# CoreCtrl.net
KiCad netlist of a schematic drawn in Altium Designer
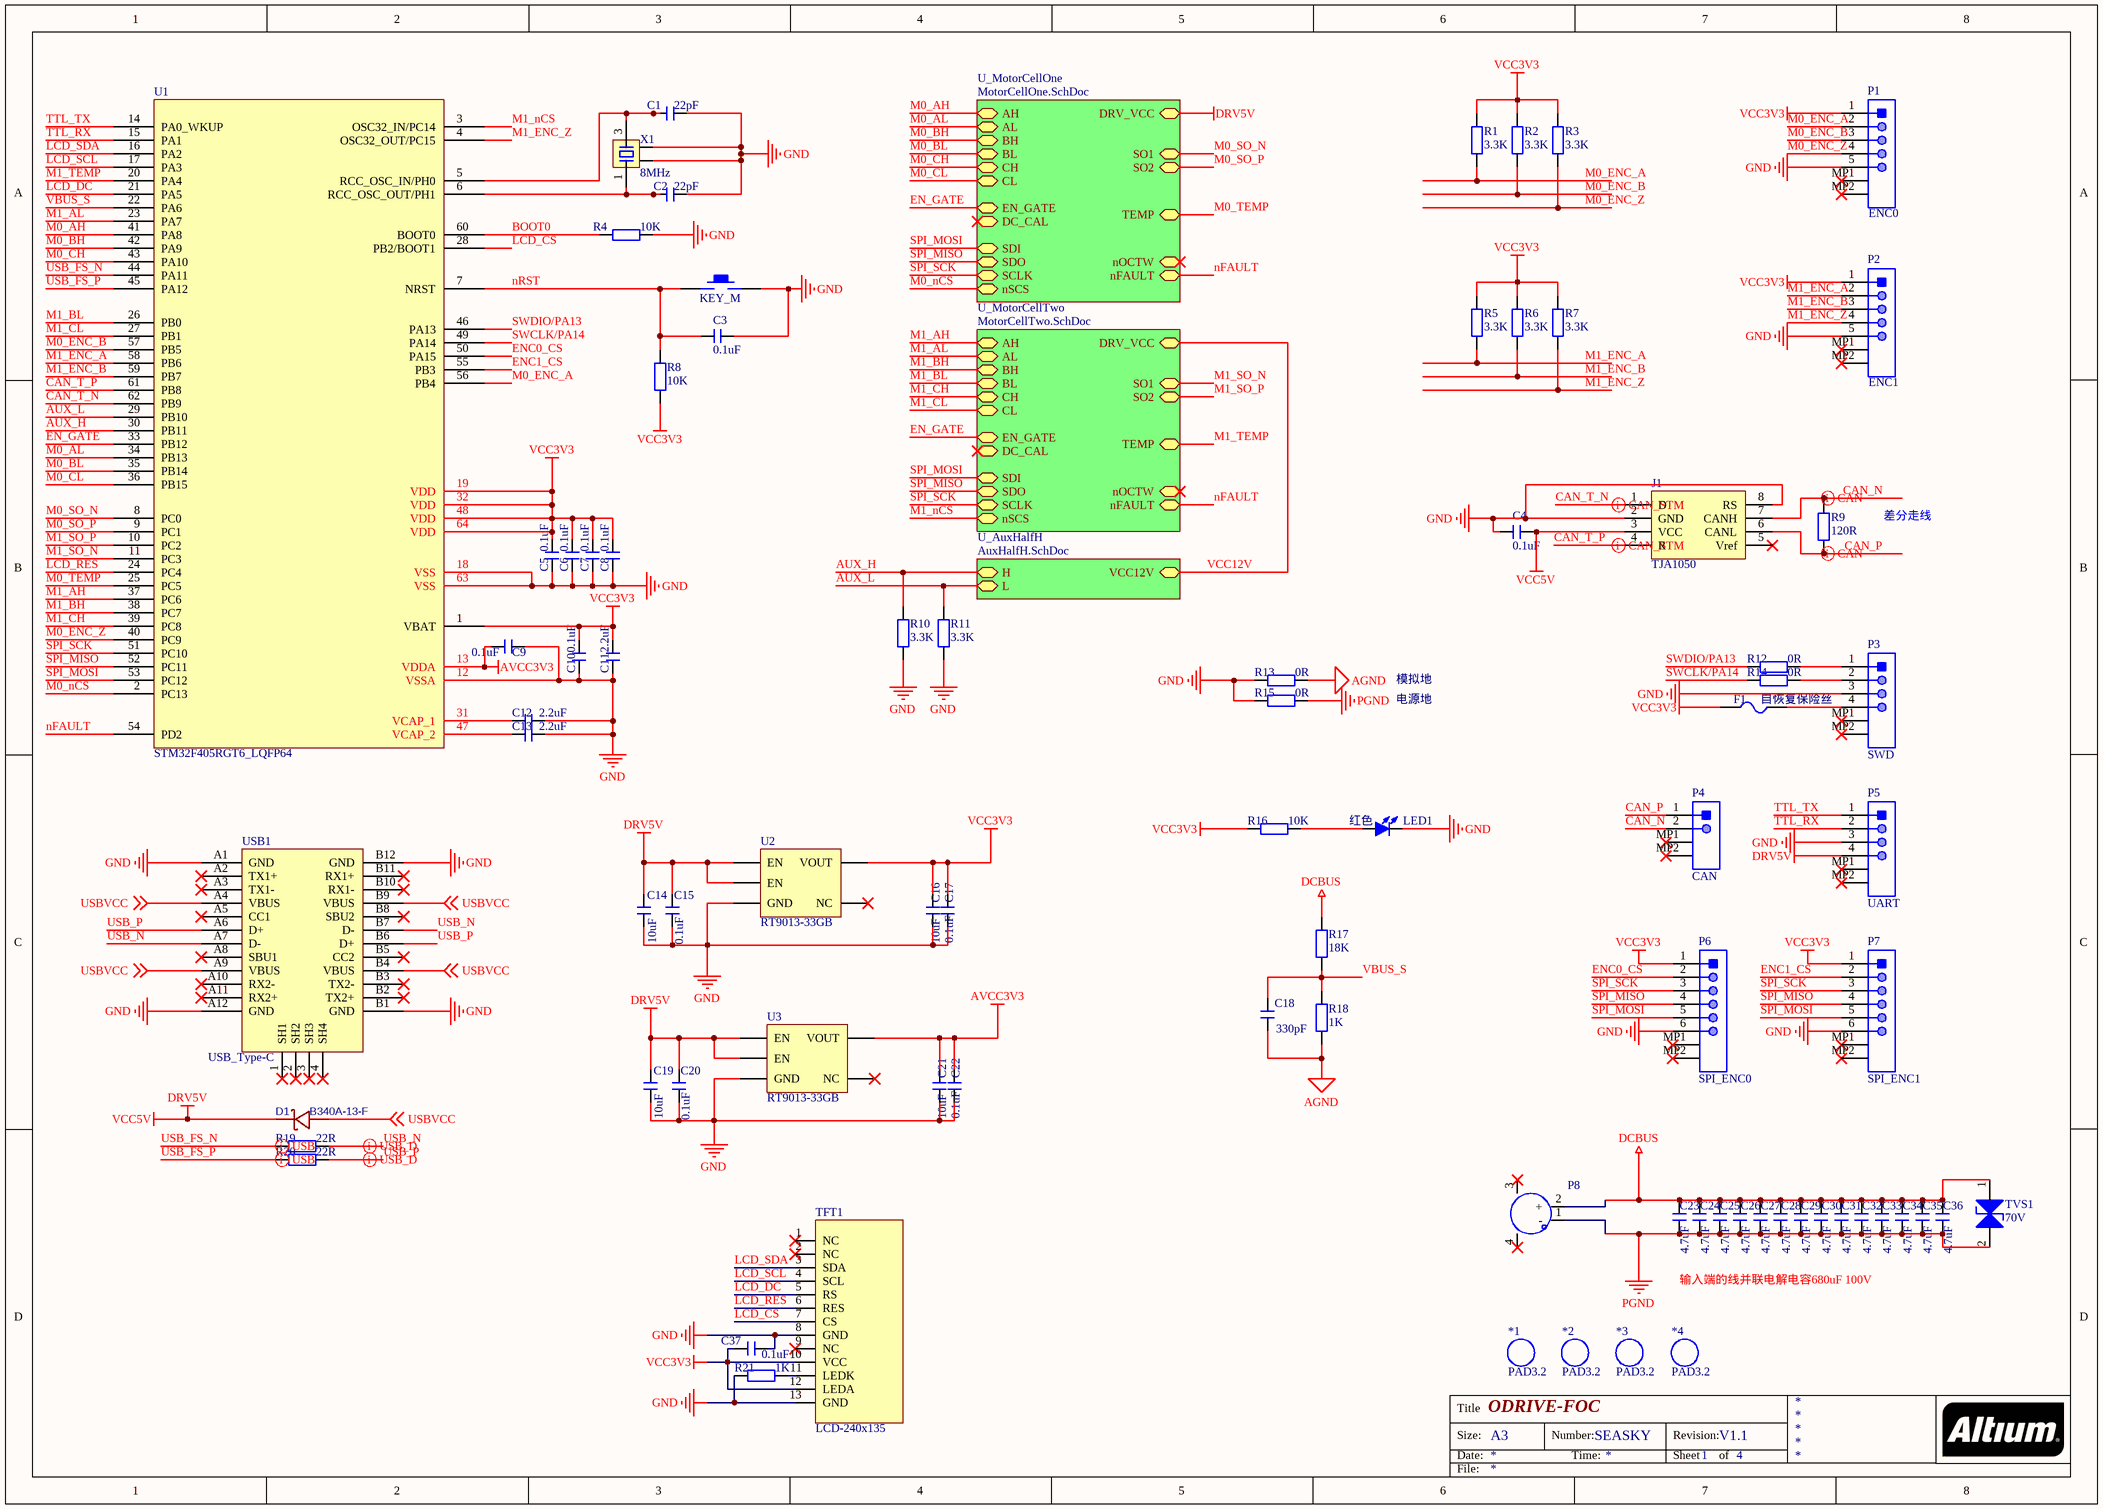
[diagram p0: CoreCtrl.SchDoc]

(export (version "E")
  (design (tool "Eeschema 10.0.6"))
  (components
    (comp (ref "*1") (value "PAD3.2") (footprint "PAD3.2") (libsource (lib "mx_pcb_library") (part "PAD3.2")))
    (comp (ref "*2") (value "PAD3.2") (footprint "PAD3.2") (libsource (lib "mx_pcb_library") (part "PAD3.2")))
    (comp (ref "*3") (value "PAD3.2") (footprint "PAD3.2") (libsource (lib "mx_pcb_library") (part "PAD3.2")))
    (comp (ref "*4") (value "PAD3.2") (footprint "PAD3.2") (libsource (lib "mx_pcb_library") (part "PAD3.2")))
    (comp (ref "C1")
      (value "22pF")
      (footprint "C 0603_L")
      (description "贴片电容")
      (libsource (lib "0.1 - 电阻-电容-电感") (part "C"))
    )
    (comp (ref "C2")
      (value "22pF")
      (footprint "C 0603_L")
      (description "贴片电容")
      (libsource (lib "0.1 - 电阻-电容-电感") (part "C"))
    )
    (comp (ref "C3")
      (value "0.1uF")
      (footprint "C 0603_L")
      (description "贴片电容")
      (libsource (lib "0.1 - 电阻-电容-电感") (part "C"))
    )
    (comp (ref "C4")
      (value "0.1uF")
      (footprint "C 0603_L")
      (description "贴片电容")
      (libsource (lib "0.1 - 电阻-电容-电感") (part "C"))
    )
    (comp (ref "C5")
      (value "0.1uF")
      (footprint "C 0603_L")
      (description "贴片电容")
      (libsource (lib "0.1 - 电阻-电容-电感") (part "C"))
    )
    (comp (ref "C6")
      (value "0.1uF")
      (footprint "C 0603_L")
      (description "贴片电容")
      (libsource (lib "0.1 - 电阻-电容-电感") (part "C"))
    )
    (comp (ref "C7")
      (value "0.1uF")
      (footprint "C 0603_L")
      (description "贴片电容")
      (libsource (lib "0.1 - 电阻-电容-电感") (part "C"))
    )
    (comp (ref "C8")
      (value "0.1uF")
      (footprint "C 0603_L")
      (description "贴片电容")
      (libsource (lib "0.1 - 电阻-电容-电感") (part "C"))
    )
    (comp (ref "C9")
      (value "0.1uF")
      (footprint "C 0603_L")
      (description "贴片电容")
      (libsource (lib "0.1 - 电阻-电容-电感") (part "C"))
    )
    (comp (ref "C10")
      (value "0.1uF")
      (footprint "C 0603_L")
      (description "贴片电容")
      (libsource (lib "0.1 - 电阻-电容-电感") (part "C"))
    )
    (comp (ref "C11")
      (value "2.2uF")
      (footprint "C 0603_L")
      (description "贴片电容")
      (libsource (lib "0.1 - 电阻-电容-电感") (part "C"))
    )
    (comp (ref "C12")
      (value "2.2uF")
      (footprint "C 0603_L")
      (description "贴片电容")
      (libsource (lib "0.1 - 电阻-电容-电感") (part "C"))
    )
    (comp (ref "C13")
      (value "2.2uF")
      (footprint "C 0603_L")
      (description "贴片电容")
      (libsource (lib "0.1 - 电阻-电容-电感") (part "C"))
    )
    (comp (ref "C14")
      (value "10uF")
      (footprint "C 0805_L")
      (description "贴片电容")
      (libsource (lib "0.1 - 电阻-电容-电感") (part "C"))
    )
    (comp (ref "C15")
      (value "0.1uF")
      (footprint "C 0805_L")
      (description "贴片电容")
      (libsource (lib "0.1 - 电阻-电容-电感") (part "C"))
    )
    (comp (ref "C16")
      (value "10uF")
      (footprint "C 0805_L")
      (description "贴片电容")
      (libsource (lib "0.1 - 电阻-电容-电感") (part "C"))
    )
    (comp (ref "C17")
      (value "0.1uF")
      (footprint "C 0805_L")
      (description "贴片电容")
      (libsource (lib "0.1 - 电阻-电容-电感") (part "C"))
    )
    (comp (ref "C18")
      (value "330pF")
      (footprint "C 0603_L")
      (description "贴片电容")
      (libsource (lib "0.1 - 电阻-电容-电感") (part "C"))
    )
    (comp (ref "C19")
      (value "10uF")
      (footprint "C 0805_L")
      (description "贴片电容")
      (libsource (lib "0.1 - 电阻-电容-电感") (part "C"))
    )
    (comp (ref "C20")
      (value "0.1uF")
      (footprint "C 0805_L")
      (description "贴片电容")
      (libsource (lib "0.1 - 电阻-电容-电感") (part "C"))
    )
    (comp (ref "C21")
      (value "10uF")
      (footprint "C 0805_L")
      (description "贴片电容")
      (libsource (lib "0.1 - 电阻-电容-电感") (part "C"))
    )
    (comp (ref "C22")
      (value "0.1uF")
      (footprint "C 0805_L")
      (description "贴片电容")
      (libsource (lib "0.1 - 电阻-电容-电感") (part "C"))
    )
    (comp (ref "C23")
      (value "4.7uF")
      (footprint "C 1210_L")
      (description "贴片电容")
      (libsource (lib "0.1 - 电阻-电容-电感") (part "C"))
    )
    (comp (ref "C24")
      (value "4.7uF")
      (footprint "C 1210_L")
      (description "贴片电容")
      (libsource (lib "0.1 - 电阻-电容-电感") (part "C"))
    )
    (comp (ref "C25")
      (value "4.7uF")
      (footprint "C 1210_L")
      (description "贴片电容")
      (libsource (lib "0.1 - 电阻-电容-电感") (part "C"))
    )
    (comp (ref "C26")
      (value "4.7uF")
      (footprint "C 1210_L")
      (description "贴片电容")
      (libsource (lib "0.1 - 电阻-电容-电感") (part "C"))
    )
    (comp (ref "C27")
      (value "4.7uF")
      (footprint "C 1210_L")
      (description "贴片电容")
      (libsource (lib "0.1 - 电阻-电容-电感") (part "C"))
    )
    (comp (ref "C28")
      (value "4.7uF")
      (footprint "C 1210_L")
      (description "贴片电容")
      (libsource (lib "0.1 - 电阻-电容-电感") (part "C"))
    )
    (comp (ref "C29")
      (value "4.7uF")
      (footprint "C 1210_L")
      (description "贴片电容")
      (libsource (lib "0.1 - 电阻-电容-电感") (part "C"))
    )
    (comp (ref "C30")
      (value "4.7uF")
      (footprint "C 1210_L")
      (description "贴片电容")
      (libsource (lib "0.1 - 电阻-电容-电感") (part "C"))
    )
    (comp (ref "C31")
      (value "4.7uF")
      (footprint "C 1210_L")
      (description "贴片电容")
      (libsource (lib "0.1 - 电阻-电容-电感") (part "C"))
    )
    (comp (ref "C32")
      (value "4.7uF")
      (footprint "C 1210_L")
      (description "贴片电容")
      (libsource (lib "0.1 - 电阻-电容-电感") (part "C"))
    )
    (comp (ref "C33")
      (value "4.7uF")
      (footprint "C 1210_L")
      (description "贴片电容")
      (libsource (lib "0.1 - 电阻-电容-电感") (part "C"))
    )
    (comp (ref "C34")
      (value "4.7uF")
      (footprint "C 1210_L")
      (description "贴片电容")
      (libsource (lib "0.1 - 电阻-电容-电感") (part "C"))
    )
    (comp (ref "C35")
      (value "4.7uF")
      (footprint "C 1210_L")
      (description "贴片电容")
      (libsource (lib "0.1 - 电阻-电容-电感") (part "C"))
    )
    (comp (ref "C36")
      (value "4.7uF")
      (footprint "C 1210_L")
      (description "贴片电容")
      (libsource (lib "0.1 - 电阻-电容-电感") (part "C"))
    )
    (comp (ref "C37")
      (value "0.1uF")
      (footprint "C 0603_L")
      (description "贴片电容")
      (libsource (lib "0.1 - 电阻-电容-电感") (part "C"))
    )
    (comp (ref "D1")
      (value "B340A-13-F")
      (footprint "SMA_L4.4-W2.6-LS5.0-RD")
      (fields (field (name "BOM_SUPPLIER PART") "C85098"))
      (libsource (lib "mx_pcb_library") (part "B340A-13-F"))
    )
    (comp (ref "F1")
      (value "自恢复保险丝")
      (footprint "FU 0603")
      (description "贴片保险丝")
      (libsource (lib "2.0 - 保险丝-晶振-光耦") (part "FU"))
    )
    (comp (ref "J1")
      (value "TJA1050")
      (footprint "SOIC-8_150mil")
      (description "CAN芯片")
      (libsource (lib "mx_pcb_library") (part "TJA1050"))
    )
    (comp (ref "LED1")
      (value "红色")
      (footprint "LED 0805G")
      (description "贴片LED")
      (libsource (lib "0.3 - LED发光二极管") (part "LED-SMD"))
    )
    (comp (ref "P1")
      (value "ENC0")
      (footprint "JST-SM05B-GHS-TB_V")
      (fields (field (name "MANUFACTURER") "JST"))
      (libsource (lib "JST GH connector") (part "SM05B-GHS-TB(LF)(SN)"))
    )
    (comp (ref "P2")
      (value "ENC1")
      (footprint "JST-SM05B-GHS-TB_V")
      (fields (field (name "MANUFACTURER") "JST"))
      (libsource (lib "JST GH connector") (part "SM05B-GHS-TB(LF)(SN)"))
    )
    (comp (ref "P3")
      (value "SWD")
      (footprint "JST-SM04B-GHS-TB_V")
      (fields (field (name "MANUFACTURER") "JST"))
      (libsource (lib "JST GH connector") (part "SM04B-GHS-TB(LF)(SN)"))
    )
    (comp (ref "P4")
      (value "CAN")
      (footprint "CONN-SMD_SM02B-GHS-TB-LF-SN")
      (libsource (lib "ODrive_Foc") (part "SM02B-GHS-TB(LF)(SN)"))
    )
    (comp (ref "P5")
      (value "UART")
      (footprint "JST-SM04B-GHS-TB_V")
      (fields (field (name "MANUFACTURER") "JST"))
      (libsource (lib "JST GH connector") (part "SM04B-GHS-TB(LF)(SN)"))
    )
    (comp (ref "P6")
      (value "SPI_ENC0")
      (footprint "JST-BM06B-GHS-TBT_V")
      (fields (field (name "MANUFACTURER") "JST"))
      (libsource (lib "JST GH connector") (part "SM06B-GHS-TB(LF)(SN)"))
    )
    (comp (ref "P7")
      (value "SPI_ENC1")
      (footprint "JST-BM06B-GHS-TBT_V")
      (fields (field (name "MANUFACTURER") "JST"))
      (libsource (lib "JST GH connector") (part "BM06B-GHS-TBT(LF)(SN)"))
    )
    (comp (ref "P8") (value "XT60PW") (footprint "XT60PW") (libsource (lib "ODrive_Foc") (part "XT60PW")))
    (comp (ref "R1")
      (value "3.3K")
      (footprint "R 0603_L")
      (description "贴片电阻")
      (libsource (lib "0.1 - 电阻-电容-电感") (part "R"))
    )
    (comp (ref "R2")
      (value "3.3K")
      (footprint "R 0603_L")
      (description "贴片电阻")
      (libsource (lib "0.1 - 电阻-电容-电感") (part "R"))
    )
    (comp (ref "R3")
      (value "3.3K")
      (footprint "R 0603_L")
      (description "贴片电阻")
      (libsource (lib "0.1 - 电阻-电容-电感") (part "R"))
    )
    (comp (ref "R4")
      (value "10K")
      (footprint "R 0603_L")
      (description "贴片电阻")
      (libsource (lib "0.1 - 电阻-电容-电感") (part "R"))
    )
    (comp (ref "R5")
      (value "3.3K")
      (footprint "R 0603_L")
      (description "贴片电阻")
      (libsource (lib "0.1 - 电阻-电容-电感") (part "R"))
    )
    (comp (ref "R6")
      (value "3.3K")
      (footprint "R 0603_L")
      (description "贴片电阻")
      (libsource (lib "0.1 - 电阻-电容-电感") (part "R"))
    )
    (comp (ref "R7")
      (value "3.3K")
      (footprint "R 0603_L")
      (description "贴片电阻")
      (libsource (lib "0.1 - 电阻-电容-电感") (part "R"))
    )
    (comp (ref "R8")
      (value "10K")
      (footprint "R 0603_L")
      (description "贴片电阻")
      (libsource (lib "0.1 - 电阻-电容-电感") (part "R"))
    )
    (comp (ref "R9")
      (value "120R")
      (footprint "R 0603_L")
      (description "贴片电阻")
      (libsource (lib "0.1 - 电阻-电容-电感") (part "R"))
    )
    (comp (ref "R10")
      (value "3.3K")
      (footprint "R 0603_L")
      (description "贴片电阻")
      (libsource (lib "0.1 - 电阻-电容-电感") (part "R"))
    )
    (comp (ref "R11")
      (value "3.3K")
      (footprint "R 0603_L")
      (description "贴片电阻")
      (libsource (lib "0.1 - 电阻-电容-电感") (part "R"))
    )
    (comp (ref "R12")
      (value "0R")
      (footprint "R 0603_L")
      (description "贴片电阻")
      (libsource (lib "0.1 - 电阻-电容-电感") (part "R"))
    )
    (comp (ref "R13")
      (value "0R")
      (footprint "R 0603_L")
      (description "贴片电阻")
      (libsource (lib "0.1 - 电阻-电容-电感") (part "R"))
    )
    (comp (ref "R14")
      (value "0R")
      (footprint "R 0603_L")
      (description "贴片电阻")
      (libsource (lib "0.1 - 电阻-电容-电感") (part "R"))
    )
    (comp (ref "R15")
      (value "0R")
      (footprint "R 0603_L")
      (description "贴片电阻")
      (libsource (lib "0.1 - 电阻-电容-电感") (part "R"))
    )
    (comp (ref "R16")
      (value "10K")
      (footprint "R 0603_L")
      (description "贴片电阻")
      (libsource (lib "0.1 - 电阻-电容-电感") (part "R"))
    )
    (comp (ref "R17")
      (value "18K")
      (footprint "R 0603_L")
      (description "贴片电阻")
      (libsource (lib "0.1 - 电阻-电容-电感") (part "R"))
    )
    (comp (ref "R18")
      (value "1K")
      (footprint "R 0603_L")
      (description "贴片电阻")
      (libsource (lib "0.1 - 电阻-电容-电感") (part "R"))
    )
    (comp (ref "R19")
      (value "22R")
      (footprint "R 0603_L")
      (description "贴片电阻")
      (libsource (lib "0.1 - 电阻-电容-电感") (part "R"))
    )
    (comp (ref "R20")
      (value "22R")
      (footprint "R 0603_L")
      (description "贴片电阻")
      (libsource (lib "0.1 - 电阻-电容-电感") (part "R"))
    )
    (comp (ref "R21")
      (value "1K")
      (footprint "R 0603_L")
      (description "贴片电阻")
      (libsource (lib "0.1 - 电阻-电容-电感") (part "R"))
    )
    (comp (ref "RST1")
      (value "KEY_M")
      (footprint "SMD-3.2*4.2")
      (libsource (lib "mx_pcb_library") (part "KEY_M"))
    )
    (comp (ref "TFT1")
      (value "LCD-240x135")
      (footprint "LCD-240x135")
      (libsource (lib "ODrive_Foc") (part "LCD-240x135"))
    )
    (comp (ref "TVS1")
      (value "70V")
      (footprint "SMA(DO-214AC)")
      (libsource (lib "mx_pcb_library") (part "SMAJ28CA"))
    )
    (comp (ref "U1")
      (value "STM32F405RGT6_LQFP64")
      (footprint "LQFP-64_10X10X05P")
      (libsource (lib "mx_pcb_library") (part "STM32F405RGT6_LQFP64"))
    )
    (comp (ref "U2")
      (value "RT9013-33GB")
      (footprint "SOT23-5M")
      (libsource (lib "mx_pcb_library") (part "RT9013-33GB"))
    )
    (comp (ref "U3")
      (value "RT9013-33GB")
      (footprint "SOT23-5M")
      (libsource (lib "mx_pcb_library") (part "RT9013-33GB"))
    )
    (comp (ref "USB1")
      (value "USB_Type-C")
      (footprint "Type-C-TOP")
      (libsource (lib "mx_pcb_library") (part "USB_Type-C"))
    )
    (comp (ref "X1")
      (value "8MHz")
      (footprint "OSC 3225-4P")
      (description "4脚无源晶振")
      (libsource (lib "2.0 - 保险丝-晶振-光耦") (part "XTAL-4P"))
    )
  )
  (nets
    (net (code "1") (name "/AUX_H") (class "Default")
      (node (ref "R10") (pin "1") (pinfunction "1_1") (pintype "passive"))
      (node (ref "U1") (pin "30") (pinfunction "PB11_30") (pintype "passive"))
    )
    (net (code "2") (name "/AUX_L") (class "Default")
      (node (ref "R11") (pin "1") (pinfunction "1_1") (pintype "passive"))
      (node (ref "U1") (pin "29") (pinfunction "PB10_29") (pintype "passive"))
    )
    (net (code "3") (name "/BOOT0") (class "Default")
      (node (ref "R4") (pin "2") (pinfunction "2_2") (pintype "passive"))
      (node (ref "U1") (pin "60") (pinfunction "BOOT0_60") (pintype "passive"))
    )
    (net (code "4") (name "/CAN_N") (class "Default")
      (node (ref "J1") (pin "7") (pinfunction "CANH_7") (pintype "passive"))
      (node (ref "P4") (pin "2") (pinfunction "2_2") (pintype "passive"))
      (node (ref "R9") (pin "1") (pinfunction "1_1") (pintype "passive"))
    )
    (net (code "5") (name "/CAN_P") (class "Default")
      (node (ref "J1") (pin "6") (pinfunction "CANL_6") (pintype "passive"))
      (node (ref "P4") (pin "1") (pinfunction "1_1") (pintype "passive"))
      (node (ref "R9") (pin "2") (pinfunction "2_2") (pintype "passive"))
    )
    (net (code "6") (name "/CAN_T_N") (class "Default")
      (node (ref "J1") (pin "1") (pinfunction "D_1") (pintype "passive"))
      (node (ref "U1") (pin "62") (pinfunction "PB9_62") (pintype "passive"))
    )
    (net (code "7") (name "/CAN_T_P") (class "Default")
      (node (ref "J1") (pin "4") (pinfunction "R_4") (pintype "passive"))
      (node (ref "U1") (pin "61") (pinfunction "PB8_61") (pintype "passive"))
    )
    (net (code "10") (name "/ENC0_CS") (class "Default")
      (node (ref "P6") (pin "2") (pinfunction "2_2") (pintype "passive"))
      (node (ref "U1") (pin "50") (pinfunction "PA15_50") (pintype "passive"))
    )
    (net (code "11") (name "/ENC1_CS") (class "Default")
      (node (ref "P7") (pin "2") (pinfunction "2_2") (pintype "passive"))
      (node (ref "U1") (pin "55") (pinfunction "PB3_55") (pintype "passive"))
    )
    (net (code "12") (name "/EN_GATE") (class "Default")
      (node (ref "U1") (pin "33") (pinfunction "PB12_33") (pintype "passive"))
    )
    (net (code "13") (name "/LCD_CS") (class "Default")
      (node (ref "TFT1") (pin "7") (pinfunction "CS_7") (pintype "passive"))
      (node (ref "U1") (pin "28") (pinfunction "PB2/BOOT1_28") (pintype "passive"))
    )
    (net (code "14") (name "/LCD_DC") (class "Default")
      (node (ref "TFT1") (pin "5") (pinfunction "RS_5") (pintype "passive"))
      (node (ref "U1") (pin "21") (pinfunction "PA5_21") (pintype "passive"))
    )
    (net (code "15") (name "/LCD_RES") (class "Default")
      (node (ref "TFT1") (pin "6") (pinfunction "RES_6") (pintype "passive"))
      (node (ref "U1") (pin "24") (pinfunction "PC4_24") (pintype "passive"))
    )
    (net (code "16") (name "/LCD_SCL") (class "Default")
      (node (ref "TFT1") (pin "4") (pinfunction "SCL_4") (pintype "passive"))
      (node (ref "U1") (pin "17") (pinfunction "PA3_17") (pintype "passive"))
    )
    (net (code "17") (name "/LCD_SDA") (class "Default")
      (node (ref "TFT1") (pin "3") (pinfunction "SDA_3") (pintype "passive"))
      (node (ref "U1") (pin "16") (pinfunction "PA2_16") (pintype "passive"))
    )
    (net (code "18") (name "/M0_AH") (class "Default")
      (node (ref "U1") (pin "41") (pinfunction "PA8_41") (pintype "passive"))
    )
    (net (code "19") (name "/M0_AL") (class "Default")
      (node (ref "U1") (pin "34") (pinfunction "PB13_34") (pintype "passive"))
    )
    (net (code "20") (name "/M0_BH") (class "Default")
      (node (ref "U1") (pin "42") (pinfunction "PA9_42") (pintype "passive"))
    )
    (net (code "21") (name "/M0_BL") (class "Default")
      (node (ref "U1") (pin "35") (pinfunction "PB14_35") (pintype "passive"))
    )
    (net (code "22") (name "/M0_CH") (class "Default")
      (node (ref "U1") (pin "43") (pinfunction "PA10_43") (pintype "passive"))
    )
    (net (code "23") (name "/M0_CL") (class "Default")
      (node (ref "U1") (pin "36") (pinfunction "PB15_36") (pintype "passive"))
    )
    (net (code "24") (name "/M0_ENC_A") (class "Default")
      (node (ref "P1") (pin "2") (pinfunction "2_2") (pintype "passive"))
      (node (ref "R1") (pin "2") (pinfunction "2_2") (pintype "passive"))
      (node (ref "U1") (pin "56") (pinfunction "PB4_56") (pintype "passive"))
    )
    (net (code "25") (name "/M0_ENC_B") (class "Default")
      (node (ref "P1") (pin "3") (pinfunction "3_3") (pintype "passive"))
      (node (ref "R2") (pin "2") (pinfunction "2_2") (pintype "passive"))
      (node (ref "U1") (pin "57") (pinfunction "PB5_57") (pintype "passive"))
    )
    (net (code "26") (name "/M0_ENC_Z") (class "Default")
      (node (ref "P1") (pin "4") (pinfunction "4_4") (pintype "passive"))
      (node (ref "R3") (pin "2") (pinfunction "2_2") (pintype "passive"))
      (node (ref "U1") (pin "40") (pinfunction "PC9_40") (pintype "passive"))
    )
    (net (code "27") (name "/M0_SO_N") (class "Default")
      (node (ref "U1") (pin "8") (pinfunction "PC0_8") (pintype "passive"))
    )
    (net (code "28") (name "/M0_SO_P") (class "Default")
      (node (ref "U1") (pin "9") (pinfunction "PC1_9") (pintype "passive"))
    )
    (net (code "29") (name "/M0_TEMP") (class "Default")
      (node (ref "U1") (pin "25") (pinfunction "PC5_25") (pintype "passive"))
    )
    (net (code "30") (name "/M0_nCS") (class "Default")
      (node (ref "U1") (pin "2") (pinfunction "PC13_2") (pintype "passive"))
    )
    (net (code "31") (name "/M1_AH") (class "Default")
      (node (ref "U1") (pin "37") (pinfunction "PC6_37") (pintype "passive"))
    )
    (net (code "32") (name "/M1_AL") (class "Default")
      (node (ref "U1") (pin "23") (pinfunction "PA7_23") (pintype "passive"))
    )
    (net (code "33") (name "/M1_BH") (class "Default")
      (node (ref "U1") (pin "38") (pinfunction "PC7_38") (pintype "passive"))
    )
    (net (code "34") (name "/M1_BL") (class "Default")
      (node (ref "U1") (pin "26") (pinfunction "PB0_26") (pintype "passive"))
    )
    (net (code "35") (name "/M1_CH") (class "Default")
      (node (ref "U1") (pin "39") (pinfunction "PC8_39") (pintype "passive"))
    )
    (net (code "36") (name "/M1_CL") (class "Default")
      (node (ref "U1") (pin "27") (pinfunction "PB1_27") (pintype "passive"))
    )
    (net (code "37") (name "/M1_ENC_A") (class "Default")
      (node (ref "P2") (pin "2") (pinfunction "2_2") (pintype "passive"))
      (node (ref "R5") (pin "2") (pinfunction "2_2") (pintype "passive"))
      (node (ref "U1") (pin "58") (pinfunction "PB6_58") (pintype "passive"))
    )
    (net (code "38") (name "/M1_ENC_B") (class "Default")
      (node (ref "P2") (pin "3") (pinfunction "3_3") (pintype "passive"))
      (node (ref "R6") (pin "2") (pinfunction "2_2") (pintype "passive"))
      (node (ref "U1") (pin "59") (pinfunction "PB7_59") (pintype "passive"))
    )
    (net (code "39") (name "/M1_ENC_Z") (class "Default")
      (node (ref "P2") (pin "4") (pinfunction "4_4") (pintype "passive"))
      (node (ref "R7") (pin "2") (pinfunction "2_2") (pintype "passive"))
      (node (ref "U1") (pin "4") (pinfunction "OSC32_OUT/PC15_4") (pintype "passive"))
    )
    (net (code "40") (name "/M1_SO_N") (class "Default")
      (node (ref "U1") (pin "11") (pinfunction "PC3_11") (pintype "passive"))
    )
    (net (code "41") (name "/M1_SO_P") (class "Default")
      (node (ref "U1") (pin "10") (pinfunction "PC2_10") (pintype "passive"))
    )
    (net (code "42") (name "/M1_TEMP") (class "Default")
      (node (ref "U1") (pin "20") (pinfunction "PA4_20") (pintype "passive"))
    )
    (net (code "43") (name "/M1_nCS") (class "Default")
      (node (ref "U1") (pin "3") (pinfunction "OSC32_IN/PC14_3") (pintype "passive"))
    )
    (net (code "44") (name "/SPI_MISO") (class "Default")
      (node (ref "P6") (pin "4") (pinfunction "4_4") (pintype "passive"))
      (node (ref "P7") (pin "4") (pinfunction "4_4") (pintype "passive"))
      (node (ref "U1") (pin "52") (pinfunction "PC11_52") (pintype "passive"))
    )
    (net (code "45") (name "/SPI_MOSI") (class "Default")
      (node (ref "P6") (pin "5") (pinfunction "5_5") (pintype "passive"))
      (node (ref "P7") (pin "5") (pinfunction "5_5") (pintype "passive"))
      (node (ref "U1") (pin "53") (pinfunction "PC12_53") (pintype "passive"))
    )
    (net (code "46") (name "/SPI_SCK") (class "Default")
      (node (ref "P6") (pin "3") (pinfunction "3_3") (pintype "passive"))
      (node (ref "P7") (pin "3") (pinfunction "3_3") (pintype "passive"))
      (node (ref "U1") (pin "51") (pinfunction "PC10_51") (pintype "passive"))
    )
    (net (code "47") (name "/SWCLK{slash}PA14") (class "Default")
      (node (ref "R14") (pin "2") (pinfunction "2_2") (pintype "passive"))
      (node (ref "U1") (pin "49") (pinfunction "PA14_49") (pintype "passive"))
    )
    (net (code "48") (name "/SWDIO{slash}PA13") (class "Default")
      (node (ref "R12") (pin "2") (pinfunction "2_2") (pintype "passive"))
      (node (ref "U1") (pin "46") (pinfunction "PA13_46") (pintype "passive"))
    )
    (net (code "49") (name "/TTL_RX") (class "Default")
      (node (ref "P5") (pin "2") (pinfunction "2_2") (pintype "passive"))
      (node (ref "U1") (pin "15") (pinfunction "PA1_15") (pintype "passive"))
    )
    (net (code "50") (name "/TTL_TX") (class "Default")
      (node (ref "P5") (pin "1") (pinfunction "1_1") (pintype "passive"))
      (node (ref "U1") (pin "14") (pinfunction "PA0_WKUP_14") (pintype "passive"))
    )
    (net (code "51") (name "/USB_FS_N") (class "Default")
      (node (ref "R19") (pin "1") (pinfunction "1_1") (pintype "passive"))
      (node (ref "U1") (pin "44") (pinfunction "PA11_44") (pintype "passive"))
    )
    (net (code "52") (name "/USB_FS_P") (class "Default")
      (node (ref "R20") (pin "1") (pinfunction "1_1") (pintype "passive"))
      (node (ref "U1") (pin "45") (pinfunction "PA12_45") (pintype "passive"))
    )
    (net (code "53") (name "/USB_N") (class "Default")
      (node (ref "R19") (pin "2") (pinfunction "2_2") (pintype "passive"))
      (node (ref "USB1") (pin "A7") (pinfunction "D-_A7") (pintype "passive"))
      (node (ref "USB1") (pin "B7") (pinfunction "D-_B7") (pintype "passive"))
    )
    (net (code "54") (name "/USB_P") (class "Default")
      (node (ref "R20") (pin "2") (pinfunction "2_2") (pintype "passive"))
      (node (ref "USB1") (pin "A6") (pinfunction "D+_A6") (pintype "passive"))
      (node (ref "USB1") (pin "B6") (pinfunction "D+_B6") (pintype "passive"))
    )
    (net (code "55") (name "/VBUS_S") (class "Default")
      (node (ref "C18") (pin "1") (pinfunction "1_1") (pintype "passive"))
      (node (ref "R17") (pin "2") (pinfunction "2_2") (pintype "passive"))
      (node (ref "R18") (pin "1") (pinfunction "1_1") (pintype "passive"))
      (node (ref "U1") (pin "22") (pinfunction "PA6_22") (pintype "passive"))
    )
    (net (code "57") (name "/nFAULT") (class "Default")
      (node (ref "U1") (pin "54") (pinfunction "PD2_54") (pintype "passive"))
    )
    (net (code "60") (name "/nRST") (class "Default")
      (node (ref "C3") (pin "2") (pinfunction "2_2") (pintype "passive"))
      (node (ref "R8") (pin "2") (pinfunction "2_2") (pintype "passive"))
      (node (ref "RST1") (pin "1") (pinfunction "1_1") (pintype "passive"))
      (node (ref "U1") (pin "7") (pinfunction "NRST_7") (pintype "passive"))
    )
    (net (code "61") (name "AGND") (class "Default")
      (node (ref "C18") (pin "2") (pinfunction "2_2") (pintype "passive"))
      (node (ref "R13") (pin "1") (pinfunction "1_1") (pintype "passive"))
      (node (ref "R18") (pin "2") (pinfunction "2_2") (pintype "passive"))
    )
    (net (code "62") (name "AVCC3V3") (class "Default")
      (node (ref "C21") (pin "2") (pinfunction "2_2") (pintype "passive"))
      (node (ref "C22") (pin "2") (pinfunction "2_2") (pintype "passive"))
      (node (ref "C9") (pin "2") (pinfunction "2_2") (pintype "passive"))
      (node (ref "U1") (pin "13") (pinfunction "VDDA_13") (pintype "passive"))
      (node (ref "U3") (pin "5") (pinfunction "VOUT_5") (pintype "passive"))
    )
    (net (code "63") (name "DCBUS") (class "Default")
      (node (ref "C23") (pin "2") (pinfunction "2_2") (pintype "passive"))
      (node (ref "C24") (pin "2") (pinfunction "2_2") (pintype "passive"))
      (node (ref "C25") (pin "2") (pinfunction "2_2") (pintype "passive"))
      (node (ref "C26") (pin "2") (pinfunction "2_2") (pintype "passive"))
      (node (ref "C27") (pin "2") (pinfunction "2_2") (pintype "passive"))
      (node (ref "C28") (pin "2") (pinfunction "2_2") (pintype "passive"))
      (node (ref "C29") (pin "2") (pinfunction "2_2") (pintype "passive"))
      (node (ref "C30") (pin "2") (pinfunction "2_2") (pintype "passive"))
      (node (ref "C31") (pin "2") (pinfunction "2_2") (pintype "passive"))
      (node (ref "C32") (pin "2") (pinfunction "2_2") (pintype "passive"))
      (node (ref "C33") (pin "2") (pinfunction "2_2") (pintype "passive"))
      (node (ref "C34") (pin "2") (pinfunction "2_2") (pintype "passive"))
      (node (ref "C35") (pin "2") (pinfunction "2_2") (pintype "passive"))
      (node (ref "C36") (pin "2") (pinfunction "2_2") (pintype "passive"))
      (node (ref "P8") (pin "2") (pinfunction "+_2") (pintype "passive"))
      (node (ref "R17") (pin "1") (pinfunction "1_1") (pintype "passive"))
      (node (ref "TVS1") (pin "1") (pinfunction "1_1") (pintype "passive"))
    )
    (net (code "64") (name "DRV5V") (class "Default")
      (node (ref "C14") (pin "2") (pinfunction "2_2") (pintype "passive"))
      (node (ref "C15") (pin "2") (pinfunction "2_2") (pintype "passive"))
      (node (ref "C19") (pin "2") (pinfunction "2_2") (pintype "passive"))
      (node (ref "C20") (pin "2") (pinfunction "2_2") (pintype "passive"))
      (node (ref "C4") (pin "1") (pinfunction "1_1") (pintype "passive"))
      (node (ref "D1") (pin "1") (pinfunction "K_1") (pintype "passive"))
      (node (ref "J1") (pin "3") (pinfunction "VCC_3") (pintype "passive"))
      (node (ref "P5") (pin "4") (pinfunction "4_4") (pintype "passive"))
      (node (ref "U2") (pin "1") (pinfunction "EN_1") (pintype "passive"))
      (node (ref "U2") (pin "3") (pinfunction "EN_3") (pintype "passive"))
      (node (ref "U3") (pin "1") (pinfunction "EN_1") (pintype "passive"))
      (node (ref "U3") (pin "3") (pinfunction "EN_3") (pintype "passive"))
    )
    (net (code "65") (name "GND") (class "Default")
      (node (ref "C1") (pin "2") (pinfunction "2_2") (pintype "passive"))
      (node (ref "C10") (pin "1") (pinfunction "1_1") (pintype "passive"))
      (node (ref "C11") (pin "1") (pinfunction "1_1") (pintype "passive"))
      (node (ref "C12") (pin "2") (pinfunction "2_2") (pintype "passive"))
      (node (ref "C13") (pin "2") (pinfunction "2_2") (pintype "passive"))
      (node (ref "C14") (pin "1") (pinfunction "1_1") (pintype "passive"))
      (node (ref "C15") (pin "1") (pinfunction "1_1") (pintype "passive"))
      (node (ref "C16") (pin "1") (pinfunction "1_1") (pintype "passive"))
      (node (ref "C17") (pin "1") (pinfunction "1_1") (pintype "passive"))
      (node (ref "C19") (pin "1") (pinfunction "1_1") (pintype "passive"))
      (node (ref "C2") (pin "2") (pinfunction "2_2") (pintype "passive"))
      (node (ref "C20") (pin "1") (pinfunction "1_1") (pintype "passive"))
      (node (ref "C21") (pin "1") (pinfunction "1_1") (pintype "passive"))
      (node (ref "C22") (pin "1") (pinfunction "1_1") (pintype "passive"))
      (node (ref "C3") (pin "1") (pinfunction "1_1") (pintype "passive"))
      (node (ref "C37") (pin "1") (pinfunction "1_1") (pintype "passive"))
      (node (ref "C4") (pin "2") (pinfunction "2_2") (pintype "passive"))
      (node (ref "C5") (pin "1") (pinfunction "1_1") (pintype "passive"))
      (node (ref "C6") (pin "1") (pinfunction "1_1") (pintype "passive"))
      (node (ref "C7") (pin "1") (pinfunction "1_1") (pintype "passive"))
      (node (ref "C8") (pin "1") (pinfunction "1_1") (pintype "passive"))
      (node (ref "C9") (pin "1") (pinfunction "1_1") (pintype "passive"))
      (node (ref "J1") (pin "2") (pinfunction "GND_2") (pintype "passive"))
      (node (ref "J1") (pin "8") (pinfunction "RS_8") (pintype "passive"))
      (node (ref "LED1") (pin "2") (pinfunction "K_2") (pintype "passive"))
      (node (ref "P1") (pin "5") (pinfunction "5_5") (pintype "passive"))
      (node (ref "P2") (pin "5") (pinfunction "5_5") (pintype "passive"))
      (node (ref "P3") (pin "3") (pinfunction "3_3") (pintype "passive"))
      (node (ref "P5") (pin "3") (pinfunction "3_3") (pintype "passive"))
      (node (ref "P6") (pin "6") (pinfunction "6_6") (pintype "passive"))
      (node (ref "P7") (pin "6") (pinfunction "6_6") (pintype "passive"))
      (node (ref "R10") (pin "2") (pinfunction "2_2") (pintype "passive"))
      (node (ref "R11") (pin "2") (pinfunction "2_2") (pintype "passive"))
      (node (ref "R13") (pin "2") (pinfunction "2_2") (pintype "passive"))
      (node (ref "R15") (pin "2") (pinfunction "2_2") (pintype "passive"))
      (node (ref "R21") (pin "1") (pinfunction "1_1") (pintype "passive"))
      (node (ref "R4") (pin "1") (pinfunction "1_1") (pintype "passive"))
      (node (ref "RST1") (pin "2") (pinfunction "2_2") (pintype "passive"))
      (node (ref "TFT1") (pin "13") (pinfunction "GND_13") (pintype "passive"))
      (node (ref "TFT1") (pin "8") (pinfunction "GND_8") (pintype "passive"))
      (node (ref "U1") (pin "12") (pinfunction "VSSA_12") (pintype "passive"))
      (node (ref "U1") (pin "18") (pinfunction "VSS_18") (pintype "passive"))
      (node (ref "U1") (pin "63") (pinfunction "VSS_63") (pintype "passive"))
      (node (ref "U2") (pin "2") (pinfunction "GND_2") (pintype "passive"))
      (node (ref "U3") (pin "2") (pinfunction "GND_2") (pintype "passive"))
      (node (ref "USB1") (pin "A1") (pinfunction "GND_A1") (pintype "passive"))
      (node (ref "USB1") (pin "A12") (pinfunction "GND_A12") (pintype "passive"))
      (node (ref "USB1") (pin "B1") (pinfunction "GND_B1") (pintype "passive"))
      (node (ref "USB1") (pin "B12") (pinfunction "GND_B12") (pintype "passive"))
      (node (ref "X1") (pin "2") (pinfunction "2_2") (pintype "passive"))
      (node (ref "X1") (pin "4") (pinfunction "4_4") (pintype "passive"))
    )
    (net (code "66") (name "Net-(F1-Pad1)") (class "Default")
      (node (ref "F1") (pin "1") (pinfunction "1_1") (pintype "passive"))
      (node (ref "P3") (pin "4") (pinfunction "4_4") (pintype "passive"))
    )
    (net (code "67") (name "Net-(LED1-A)") (class "Default")
      (node (ref "LED1") (pin "1") (pinfunction "A_1") (pintype "passive"))
      (node (ref "R16") (pin "2") (pinfunction "2_2") (pintype "passive"))
    )
    (net (code "68") (name "Net-(P3-Pad1)") (class "Default")
      (node (ref "P3") (pin "1") (pinfunction "1_1") (pintype "passive"))
      (node (ref "R12") (pin "1") (pinfunction "1_1") (pintype "passive"))
    )
    (net (code "69") (name "Net-(P3-Pad2)") (class "Default")
      (node (ref "P3") (pin "2") (pinfunction "2_2") (pintype "passive"))
      (node (ref "R14") (pin "1") (pinfunction "1_1") (pintype "passive"))
    )
    (net (code "70") (name "Net-(TFT1-LEDK)") (class "Default")
      (node (ref "R21") (pin "2") (pinfunction "2_2") (pintype "passive"))
      (node (ref "TFT1") (pin "11") (pinfunction "LEDK_11") (pintype "passive"))
    )
    (net (code "71") (name "Net-(U1-RCC_OSC_IN{slash}PH0)") (class "Default")
      (node (ref "C1") (pin "1") (pinfunction "1_1") (pintype "passive"))
      (node (ref "U1") (pin "5") (pinfunction "RCC_OSC_IN/PH0_5") (pintype "passive"))
      (node (ref "X1") (pin "3") (pinfunction "3_3") (pintype "passive"))
    )
    (net (code "72") (name "Net-(U1-RCC_OSC_OUT{slash}PH1)") (class "Default")
      (node (ref "C2") (pin "1") (pinfunction "1_1") (pintype "passive"))
      (node (ref "U1") (pin "6") (pinfunction "RCC_OSC_OUT/PH1_6") (pintype "passive"))
      (node (ref "X1") (pin "1") (pinfunction "1_1") (pintype "passive"))
    )
    (net (code "73") (name "Net-(U1-VCAP_1)") (class "Default")
      (node (ref "C12") (pin "1") (pinfunction "1_1") (pintype "passive"))
      (node (ref "U1") (pin "31") (pinfunction "VCAP_1_31") (pintype "passive"))
    )
    (net (code "74") (name "Net-(U1-VCAP_2)") (class "Default")
      (node (ref "C13") (pin "1") (pinfunction "1_1") (pintype "passive"))
      (node (ref "U1") (pin "47") (pinfunction "VCAP_2_47") (pintype "passive"))
    )
    (net (code "75") (name "PGND") (class "Default")
      (node (ref "C23") (pin "1") (pinfunction "1_1") (pintype "passive"))
      (node (ref "C24") (pin "1") (pinfunction "1_1") (pintype "passive"))
      (node (ref "C25") (pin "1") (pinfunction "1_1") (pintype "passive"))
      (node (ref "C26") (pin "1") (pinfunction "1_1") (pintype "passive"))
      (node (ref "C27") (pin "1") (pinfunction "1_1") (pintype "passive"))
      (node (ref "C28") (pin "1") (pinfunction "1_1") (pintype "passive"))
      (node (ref "C29") (pin "1") (pinfunction "1_1") (pintype "passive"))
      (node (ref "C30") (pin "1") (pinfunction "1_1") (pintype "passive"))
      (node (ref "C31") (pin "1") (pinfunction "1_1") (pintype "passive"))
      (node (ref "C32") (pin "1") (pinfunction "1_1") (pintype "passive"))
      (node (ref "C33") (pin "1") (pinfunction "1_1") (pintype "passive"))
      (node (ref "C34") (pin "1") (pinfunction "1_1") (pintype "passive"))
      (node (ref "C35") (pin "1") (pinfunction "1_1") (pintype "passive"))
      (node (ref "C36") (pin "1") (pinfunction "1_1") (pintype "passive"))
      (node (ref "P8") (pin "1") (pinfunction "-_1") (pintype "passive"))
      (node (ref "R15") (pin "1") (pinfunction "1_1") (pintype "passive"))
      (node (ref "TVS1") (pin "2") (pinfunction "2_2") (pintype "passive"))
    )
    (net (code "76") (name "USBVCC") (class "Default")
      (node (ref "D1") (pin "2") (pinfunction "A_2") (pintype "passive"))
      (node (ref "USB1") (pin "A4") (pinfunction "VBUS_A4") (pintype "passive"))
      (node (ref "USB1") (pin "A9") (pinfunction "VBUS_A9") (pintype "passive"))
      (node (ref "USB1") (pin "B4") (pinfunction "VBUS_B4") (pintype "passive"))
      (node (ref "USB1") (pin "B9") (pinfunction "VBUS_B9") (pintype "passive"))
    )
    (net (code "77") (name "VCC3V3") (class "Default")
      (node (ref "C10") (pin "2") (pinfunction "2_2") (pintype "passive"))
      (node (ref "C11") (pin "2") (pinfunction "2_2") (pintype "passive"))
      (node (ref "C16") (pin "2") (pinfunction "2_2") (pintype "passive"))
      (node (ref "C17") (pin "2") (pinfunction "2_2") (pintype "passive"))
      (node (ref "C37") (pin "2") (pinfunction "2_2") (pintype "passive"))
      (node (ref "C5") (pin "2") (pinfunction "2_2") (pintype "passive"))
      (node (ref "C6") (pin "2") (pinfunction "2_2") (pintype "passive"))
      (node (ref "C7") (pin "2") (pinfunction "2_2") (pintype "passive"))
      (node (ref "C8") (pin "2") (pinfunction "2_2") (pintype "passive"))
      (node (ref "F1") (pin "2") (pinfunction "2_2") (pintype "passive"))
      (node (ref "P1") (pin "1") (pinfunction "1_1") (pintype "passive"))
      (node (ref "P2") (pin "1") (pinfunction "1_1") (pintype "passive"))
      (node (ref "P6") (pin "1") (pinfunction "1_1") (pintype "passive"))
      (node (ref "P7") (pin "1") (pinfunction "1_1") (pintype "passive"))
      (node (ref "R1") (pin "1") (pinfunction "1_1") (pintype "passive"))
      (node (ref "R16") (pin "1") (pinfunction "1_1") (pintype "passive"))
      (node (ref "R2") (pin "1") (pinfunction "1_1") (pintype "passive"))
      (node (ref "R3") (pin "1") (pinfunction "1_1") (pintype "passive"))
      (node (ref "R5") (pin "1") (pinfunction "1_1") (pintype "passive"))
      (node (ref "R6") (pin "1") (pinfunction "1_1") (pintype "passive"))
      (node (ref "R7") (pin "1") (pinfunction "1_1") (pintype "passive"))
      (node (ref "R8") (pin "1") (pinfunction "1_1") (pintype "passive"))
      (node (ref "TFT1") (pin "10") (pinfunction "VCC_10") (pintype "passive"))
      (node (ref "TFT1") (pin "12") (pinfunction "LEDA_12") (pintype "passive"))
      (node (ref "U1") (pin "1") (pinfunction "VBAT_1") (pintype "passive"))
      (node (ref "U1") (pin "19") (pinfunction "VDD_19") (pintype "passive"))
      (node (ref "U1") (pin "32") (pinfunction "VDD_32") (pintype "passive"))
      (node (ref "U1") (pin "48") (pinfunction "VDD_48") (pintype "passive"))
      (node (ref "U1") (pin "64") (pinfunction "VDD_64") (pintype "passive"))
      (node (ref "U2") (pin "5") (pinfunction "VOUT_5") (pintype "passive"))
    )
    (net (code "78") (name "unconnected-(J1-Vref-Pad5)") (class "Default")
      (node (ref "J1") (pin "5") (pinfunction "Vref_5") (pintype "passive+no_connect"))
    )
    (net (code "79") (name "unconnected-(P1-PadMP1)") (class "Default")
      (node (ref "P1") (pin "MP1") (pinfunction "MP1_MP1") (pintype "passive+no_connect"))
    )
    (net (code "80") (name "unconnected-(P1-PadMP2)") (class "Default")
      (node (ref "P1") (pin "MP2") (pinfunction "MP2_MP2") (pintype "passive+no_connect"))
    )
    (net (code "81") (name "unconnected-(P2-PadMP1)") (class "Default")
      (node (ref "P2") (pin "MP1") (pinfunction "MP1_MP1") (pintype "passive+no_connect"))
    )
    (net (code "82") (name "unconnected-(P2-PadMP2)") (class "Default")
      (node (ref "P2") (pin "MP2") (pinfunction "MP2_MP2") (pintype "passive+no_connect"))
    )
    (net (code "83") (name "unconnected-(P3-PadMP1)") (class "Default")
      (node (ref "P3") (pin "MP1") (pinfunction "MP1_MP1") (pintype "passive+no_connect"))
    )
    (net (code "84") (name "unconnected-(P3-PadMP2)") (class "Default")
      (node (ref "P3") (pin "MP2") (pinfunction "MP2_MP2") (pintype "passive+no_connect"))
    )
    (net (code "85") (name "unconnected-(P4-3-PadMP1)") (class "Default")
      (node (ref "P4") (pin "MP1") (pinfunction "3_MP1") (pintype "passive+no_connect"))
    )
    (net (code "86") (name "unconnected-(P4-PadMP2)") (class "Default")
      (node (ref "P4") (pin "MP2") (pinfunction "MP2_MP2") (pintype "passive+no_connect"))
    )
    (net (code "87") (name "unconnected-(P5-PadMP1)") (class "Default")
      (node (ref "P5") (pin "MP1") (pinfunction "MP1_MP1") (pintype "passive+no_connect"))
    )
    (net (code "88") (name "unconnected-(P5-PadMP2)") (class "Default")
      (node (ref "P5") (pin "MP2") (pinfunction "MP2_MP2") (pintype "passive+no_connect"))
    )
    (net (code "89") (name "unconnected-(P6-PadMP1)") (class "Default")
      (node (ref "P6") (pin "MP1") (pinfunction "MP1_MP1") (pintype "passive+no_connect"))
    )
    (net (code "90") (name "unconnected-(P6-PadMP2)") (class "Default")
      (node (ref "P6") (pin "MP2") (pinfunction "MP2_MP2") (pintype "passive+no_connect"))
    )
    (net (code "91") (name "unconnected-(P7-PadMP1)") (class "Default")
      (node (ref "P7") (pin "MP1") (pinfunction "MP1_MP1") (pintype "passive+no_connect"))
    )
    (net (code "92") (name "unconnected-(P7-PadMP2)") (class "Default")
      (node (ref "P7") (pin "MP2") (pinfunction "MP2_MP2") (pintype "passive+no_connect"))
    )
    (net (code "93") (name "unconnected-(P8-Pad3)") (class "Default")
      (node (ref "P8") (pin "3") (pinfunction "3_3") (pintype "passive+no_connect"))
    )
    (net (code "94") (name "unconnected-(P8-Pad4)") (class "Default")
      (node (ref "P8") (pin "4") (pinfunction "4_4") (pintype "passive+no_connect"))
    )
    (net (code "95") (name "unconnected-(TFT1-NC-Pad1)") (class "Default")
      (node (ref "TFT1") (pin "1") (pinfunction "NC_1") (pintype "passive+no_connect"))
    )
    (net (code "96") (name "unconnected-(TFT1-NC-Pad2)") (class "Default")
      (node (ref "TFT1") (pin "2") (pinfunction "NC_2") (pintype "passive+no_connect"))
    )
    (net (code "97") (name "unconnected-(TFT1-NC-Pad9)") (class "Default")
      (node (ref "TFT1") (pin "9") (pinfunction "NC_9") (pintype "passive+no_connect"))
    )
    (net (code "98") (name "unconnected-(U2-NC-Pad4)") (class "Default")
      (node (ref "U2") (pin "4") (pinfunction "NC_4") (pintype "passive+no_connect"))
    )
    (net (code "99") (name "unconnected-(U3-NC-Pad4)") (class "Default")
      (node (ref "U3") (pin "4") (pinfunction "NC_4") (pintype "passive+no_connect"))
    )
    (net (code "100") (name "unconnected-(USB1-CC1-PadA5)") (class "Default")
      (node (ref "USB1") (pin "A5") (pinfunction "CC1_A5") (pintype "passive+no_connect"))
    )
    (net (code "101") (name "unconnected-(USB1-CC2-PadB5)") (class "Default")
      (node (ref "USB1") (pin "B5") (pinfunction "CC2_B5") (pintype "passive+no_connect"))
    )
    (net (code "102") (name "unconnected-(USB1-RX1+-PadB11)") (class "Default")
      (node (ref "USB1") (pin "B11") (pinfunction "RX1+_B11") (pintype "passive+no_connect"))
    )
    (net (code "103") (name "unconnected-(USB1-RX1--PadB10)") (class "Default")
      (node (ref "USB1") (pin "B10") (pinfunction "RX1-_B10") (pintype "passive+no_connect"))
    )
    (net (code "104") (name "unconnected-(USB1-RX2+-PadA11)") (class "Default")
      (node (ref "USB1") (pin "A11") (pinfunction "RX2+_A11") (pintype "passive+no_connect"))
    )
    (net (code "105") (name "unconnected-(USB1-RX2--PadA10)") (class "Default")
      (node (ref "USB1") (pin "A10") (pinfunction "RX2-_A10") (pintype "passive+no_connect"))
    )
    (net (code "106") (name "unconnected-(USB1-SBU1-PadA8)") (class "Default")
      (node (ref "USB1") (pin "A8") (pinfunction "SBU1_A8") (pintype "passive+no_connect"))
    )
    (net (code "107") (name "unconnected-(USB1-SBU2-PadB8)") (class "Default")
      (node (ref "USB1") (pin "B8") (pinfunction "SBU2_B8") (pintype "passive+no_connect"))
    )
    (net (code "108") (name "unconnected-(USB1-SH1-Pad1)") (class "Default")
      (node (ref "USB1") (pin "1") (pinfunction "SH1_1") (pintype "passive+no_connect"))
    )
    (net (code "109") (name "unconnected-(USB1-SH2-Pad2)") (class "Default")
      (node (ref "USB1") (pin "2") (pinfunction "SH2_2") (pintype "passive+no_connect"))
    )
    (net (code "110") (name "unconnected-(USB1-SH3-Pad3)") (class "Default")
      (node (ref "USB1") (pin "3") (pinfunction "SH3_3") (pintype "passive+no_connect"))
    )
    (net (code "111") (name "unconnected-(USB1-SH4-Pad4)") (class "Default")
      (node (ref "USB1") (pin "4") (pinfunction "SH4_4") (pintype "passive+no_connect"))
    )
    (net (code "112") (name "unconnected-(USB1-TX1+-PadA2)") (class "Default")
      (node (ref "USB1") (pin "A2") (pinfunction "TX1+_A2") (pintype "passive+no_connect"))
    )
    (net (code "113") (name "unconnected-(USB1-TX1--PadA3)") (class "Default")
      (node (ref "USB1") (pin "A3") (pinfunction "TX1-_A3") (pintype "passive+no_connect"))
    )
    (net (code "114") (name "unconnected-(USB1-TX2+-PadB2)") (class "Default")
      (node (ref "USB1") (pin "B2") (pinfunction "TX2+_B2") (pintype "passive+no_connect"))
    )
    (net (code "115") (name "unconnected-(USB1-TX2--PadB3)") (class "Default")
      (node (ref "USB1") (pin "B3") (pinfunction "TX2-_B3") (pintype "passive+no_connect"))
    )
  )
)
